# E18-MS1.net
KiCad netlist of a schematic drawn in Altium Designer
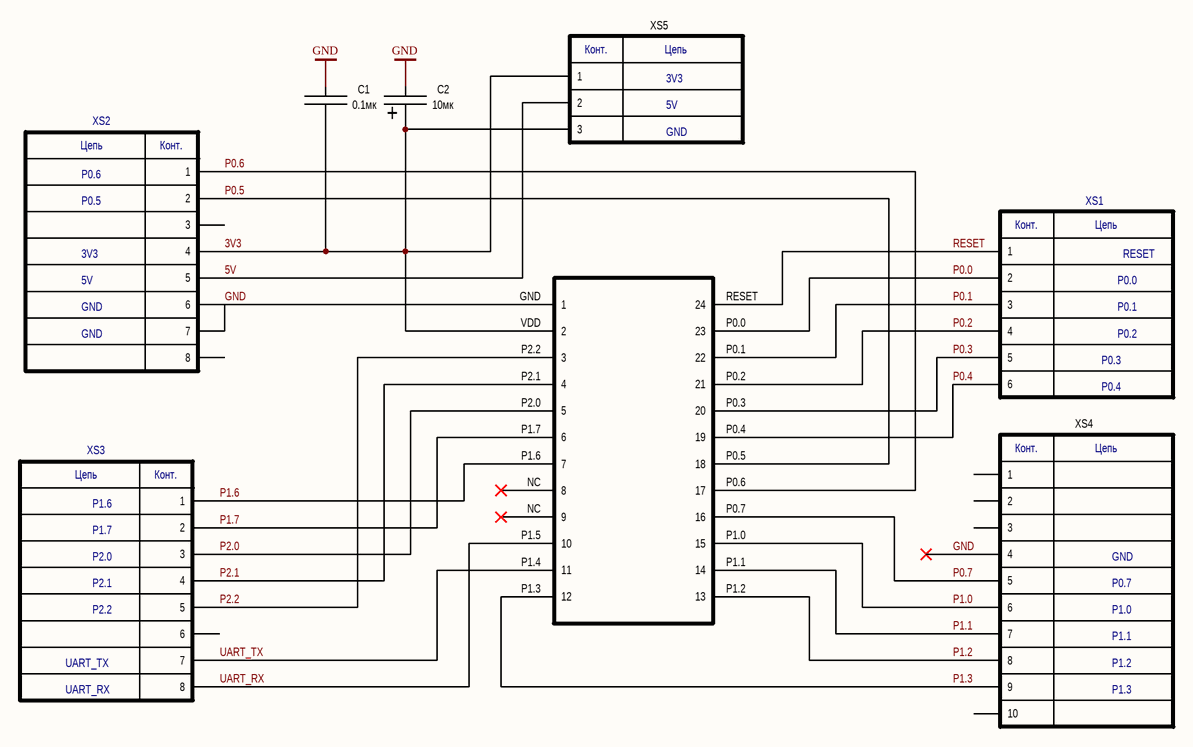
[diagram p0: E18-MS1.SchDoc]

(export (version "E")
  (design (tool "Eeschema 10.0.6"))
  (components
    (comp (ref "C1")
      (value "0.1мк")
      (footprint "C0603")
      (fields (field (name "TOLERANCE") "%") (field (name "VOLTAGE") "В") (field (name "Comment") "C"))
      (libsource (lib "5ko") (part "C"))
    )
    (comp (ref "C2")
      (value "10мк")
      (footprint "Case A")
      (fields (field (name "TOLERANCE") "%") (field (name "VOLTAGE") "V") (field (name "Comment") "C_el"))
      (libsource (lib "5ko") (part "C_el"))
    )
    (comp (ref "MCU")
      (value "E18-MS1-PCB")
      (footprint "E18-MS1")
      (libsource (lib "Schlib1") (part "E18-MS1-PCB"))
    )
    (comp (ref "XS1") (value "6pin") (footprint "PLS-6") (libsource (lib "5ko") (part "6pin")))
    (comp (ref "XS2") (value "8pin") (footprint "PLS-8") (libsource (lib "5ko") (part "8pin")))
    (comp (ref "XS3") (value "8pin") (footprint "PLS-8") (libsource (lib "5ko") (part "8pin")))
    (comp (ref "XS4") (value "10pin") (footprint "PLS-10") (libsource (lib "5ko") (part "10pin")))
    (comp (ref "XS5") (value "3pin") (footprint "PLS-3") (libsource (lib "5ko") (part "3pin")))
  )
  (nets
    (net (code "1") (name "/3V3") (class "Default")
      (node (ref "C1") (pin "1") (pinfunction "1_1") (pintype "passive"))
      (node (ref "C2") (pin "1") (pinfunction "1_1") (pintype "passive"))
      (node (ref "MCU") (pin "VDD") (pinfunction "2_VDD") (pintype "passive"))
      (node (ref "XS2") (pin "4") (pinfunction "4_4") (pintype "passive"))
      (node (ref "XS5") (pin "1") (pinfunction "1_1") (pintype "passive"))
      (node (ref "XS5") (pin "3") (pinfunction "3_3") (pintype "passive"))
    )
    (net (code "2") (name "/5V") (class "Default")
      (node (ref "XS2") (pin "5") (pinfunction "5_5") (pintype "passive"))
      (node (ref "XS5") (pin "2") (pinfunction "2_2") (pintype "passive"))
    )
    (net (code "3") (name "/P0.0") (class "Default")
      (node (ref "MCU") (pin "P0.0") (pinfunction "23_P0.0") (pintype "passive"))
      (node (ref "XS1") (pin "2") (pinfunction "2_2") (pintype "passive"))
    )
    (net (code "4") (name "/P0.1") (class "Default")
      (node (ref "MCU") (pin "P0.1") (pinfunction "22_P0.1") (pintype "passive"))
      (node (ref "XS1") (pin "3") (pinfunction "3_3") (pintype "passive"))
    )
    (net (code "5") (name "/P0.2") (class "Default")
      (node (ref "MCU") (pin "P0.2") (pinfunction "21_P0.2") (pintype "passive"))
      (node (ref "XS1") (pin "4") (pinfunction "4_4") (pintype "passive"))
    )
    (net (code "6") (name "/P0.3") (class "Default")
      (node (ref "MCU") (pin "P0.3") (pinfunction "20_P0.3") (pintype "passive"))
      (node (ref "XS1") (pin "5") (pinfunction "5_5") (pintype "passive"))
    )
    (net (code "7") (name "/P0.4") (class "Default")
      (node (ref "MCU") (pin "P0.4") (pinfunction "19_P0.4") (pintype "passive"))
      (node (ref "XS1") (pin "6") (pinfunction "6_6") (pintype "passive"))
    )
    (net (code "8") (name "/P0.5") (class "Default")
      (node (ref "MCU") (pin "P0.5") (pinfunction "18_P0.5") (pintype "passive"))
      (node (ref "XS2") (pin "2") (pinfunction "2_2") (pintype "passive"))
    )
    (net (code "9") (name "/P0.6") (class "Default")
      (node (ref "MCU") (pin "P0.6") (pinfunction "17_P0.6") (pintype "passive"))
      (node (ref "XS2") (pin "1") (pinfunction "1_1") (pintype "passive"))
    )
    (net (code "10") (name "/P0.7") (class "Default")
      (node (ref "MCU") (pin "P0.7") (pinfunction "16_P0.7") (pintype "passive"))
      (node (ref "XS4") (pin "5") (pinfunction "5_5") (pintype "passive"))
    )
    (net (code "11") (name "/P1.0") (class "Default")
      (node (ref "MCU") (pin "P1.0") (pinfunction "15_P1.0") (pintype "passive"))
      (node (ref "XS4") (pin "6") (pinfunction "6_6") (pintype "passive"))
    )
    (net (code "12") (name "/P1.1") (class "Default")
      (node (ref "MCU") (pin "P1.1") (pinfunction "14_P1.1") (pintype "passive"))
      (node (ref "XS4") (pin "7") (pinfunction "7_7") (pintype "passive"))
    )
    (net (code "13") (name "/P1.2") (class "Default")
      (node (ref "MCU") (pin "P1.2") (pinfunction "13_P1.2") (pintype "passive"))
      (node (ref "XS4") (pin "8") (pinfunction "8_8") (pintype "passive"))
    )
    (net (code "14") (name "/P1.3") (class "Default")
      (node (ref "MCU") (pin "P1.3") (pinfunction "12_P1.3") (pintype "passive"))
      (node (ref "XS4") (pin "9") (pinfunction "9_9") (pintype "passive"))
    )
    (net (code "15") (name "/P1.6") (class "Default")
      (node (ref "MCU") (pin "P1.6") (pinfunction "7_P1.6") (pintype "passive"))
      (node (ref "XS3") (pin "1") (pinfunction "1_1") (pintype "passive"))
    )
    (net (code "16") (name "/P1.7") (class "Default")
      (node (ref "MCU") (pin "P1.7") (pinfunction "6_P1.7") (pintype "passive"))
      (node (ref "XS3") (pin "2") (pinfunction "2_2") (pintype "passive"))
    )
    (net (code "17") (name "/P2.0") (class "Default")
      (node (ref "MCU") (pin "P2.0") (pinfunction "5_P2.0") (pintype "passive"))
      (node (ref "XS3") (pin "3") (pinfunction "3_3") (pintype "passive"))
    )
    (net (code "18") (name "/P2.1") (class "Default")
      (node (ref "MCU") (pin "P2.1") (pinfunction "4_P2.1") (pintype "passive"))
      (node (ref "XS3") (pin "4") (pinfunction "4_4") (pintype "passive"))
    )
    (net (code "19") (name "/P2.2") (class "Default")
      (node (ref "MCU") (pin "P2.2") (pinfunction "3_P2.2") (pintype "passive"))
      (node (ref "XS3") (pin "5") (pinfunction "5_5") (pintype "passive"))
    )
    (net (code "20") (name "/RESET") (class "Default")
      (node (ref "MCU") (pin "RESET") (pinfunction "24_RESET") (pintype "passive"))
      (node (ref "XS1") (pin "1") (pinfunction "1_1") (pintype "passive"))
    )
    (net (code "21") (name "/UART_RX") (class "Default")
      (node (ref "MCU") (pin "P1.5") (pinfunction "10_P1.5") (pintype "passive"))
      (node (ref "XS3") (pin "8") (pinfunction "8_8") (pintype "passive"))
    )
    (net (code "22") (name "/UART_TX") (class "Default")
      (node (ref "MCU") (pin "P1.4") (pinfunction "11_P1.4") (pintype "passive"))
      (node (ref "XS3") (pin "7") (pinfunction "7_7") (pintype "passive"))
    )
    (net (code "23") (name "GND") (class "Default")
      (node (ref "C1") (pin "2") (pinfunction "2_2") (pintype "passive"))
      (node (ref "C2") (pin "2") (pinfunction "2_2") (pintype "passive"))
      (node (ref "MCU") (pin "GND") (pinfunction "1_GND") (pintype "passive"))
      (node (ref "XS2") (pin "6") (pinfunction "6_6") (pintype "passive"))
      (node (ref "XS2") (pin "7") (pinfunction "7_7") (pintype "passive"))
      (node (ref "XS4") (pin "4") (pinfunction "4_4") (pintype "passive"))
    )
    (net (code "24") (name "unconnected-(MCU-8-PadNC)") (class "Default")
      (node (ref "MCU") (pin "NC") (pinfunction "8_NC") (pintype "passive+no_connect"))
    )
    (net (code "25") (name "unconnected-(MCU-9-PadNC)") (class "Default")
      (node (ref "MCU") (pin "NC") (pinfunction "9_NC") (pintype "passive+no_connect"))
    )
    (net (code "26") (name "unconnected-(XS2-Pad3)") (class "Default")
      (node (ref "XS2") (pin "3") (pinfunction "3_3") (pintype "passive"))
    )
    (net (code "27") (name "unconnected-(XS2-Pad8)") (class "Default")
      (node (ref "XS2") (pin "8") (pinfunction "8_8") (pintype "passive"))
    )
    (net (code "28") (name "unconnected-(XS3-Pad6)") (class "Default")
      (node (ref "XS3") (pin "6") (pinfunction "6_6") (pintype "passive"))
    )
    (net (code "29") (name "unconnected-(XS4-Pad1)") (class "Default")
      (node (ref "XS4") (pin "1") (pinfunction "1_1") (pintype "passive"))
    )
    (net (code "30") (name "unconnected-(XS4-Pad2)") (class "Default")
      (node (ref "XS4") (pin "2") (pinfunction "2_2") (pintype "passive"))
    )
    (net (code "31") (name "unconnected-(XS4-Pad3)") (class "Default")
      (node (ref "XS4") (pin "3") (pinfunction "3_3") (pintype "passive"))
    )
    (net (code "32") (name "unconnected-(XS4-Pad10)") (class "Default")
      (node (ref "XS4") (pin "10") (pinfunction "10_10") (pintype "passive"))
    )
  )
)
